# main.net
KiCad netlist of a schematic drawn in EAGLE
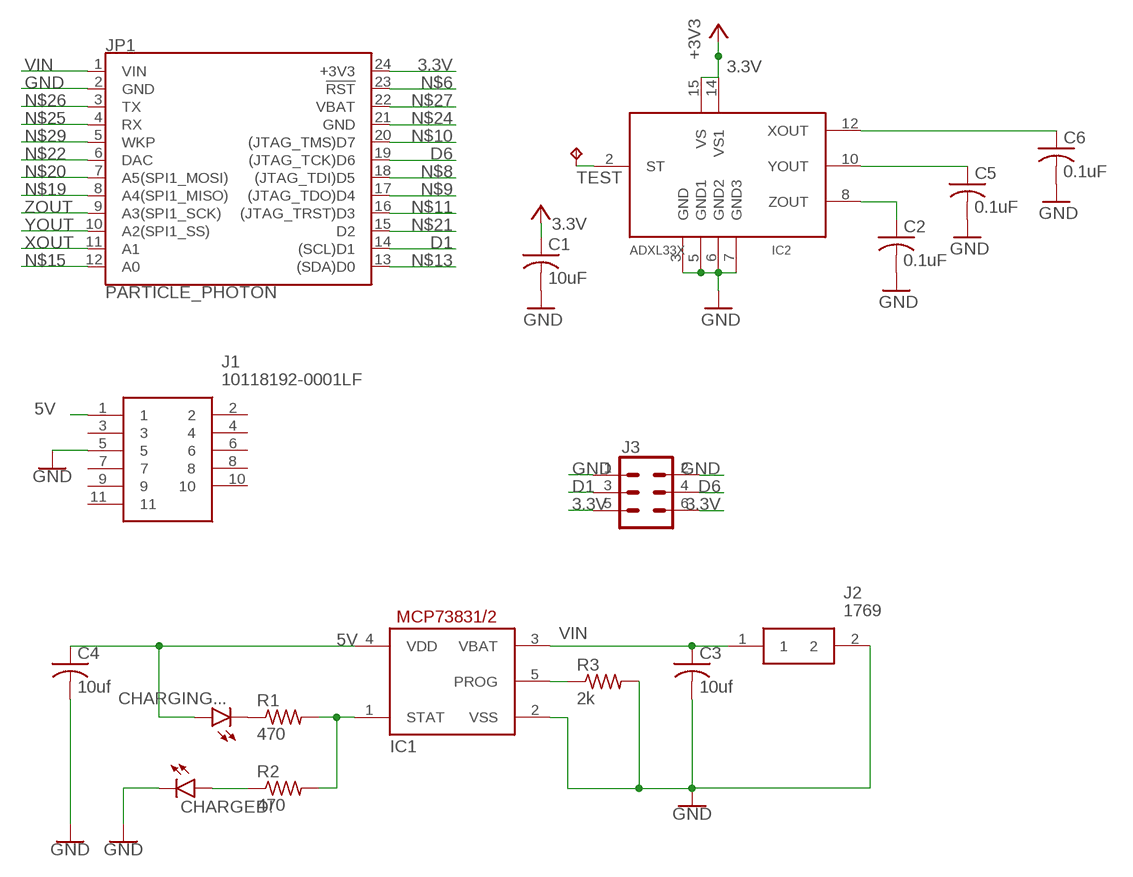
[diagram p0: schematic, sheet 1]

(export (version "E")
  (design (tool "Eeschema 10.0.6"))
  (components
    (comp (ref "C1")
      (value "10uF")
      (footprint "eagle-import:ADAFRUIT_C1206K")
      (libsource (lib "eagle-import") (part "ADAFRUIT_C-USC1206K"))
    )
    (comp (ref "C2")
      (value "0.1uF")
      (footprint "eagle-import:ADAFRUIT_C1206K")
      (libsource (lib "eagle-import") (part "ADAFRUIT_C-USC1206K"))
    )
    (comp (ref "C3")
      (value "10uf")
      (footprint "eagle-import:C1206K")
      (libsource (lib "eagle-import") (part "C-USC1206K"))
    )
    (comp (ref "C4")
      (value "10uf")
      (footprint "eagle-import:C1206K")
      (libsource (lib "eagle-import") (part "C-USC1206K"))
    )
    (comp (ref "C5")
      (value "0.1uF")
      (footprint "eagle-import:ADAFRUIT_C1206K")
      (libsource (lib "eagle-import") (part "ADAFRUIT_C-USC1206K"))
    )
    (comp (ref "C6")
      (value "0.1uF")
      (footprint "eagle-import:ADAFRUIT_C1206K")
      (libsource (lib "eagle-import") (part "ADAFRUIT_C-USC1206K"))
    )
    (comp (ref "CHARGED!")
      (value "green")
      (footprint "eagle-import:FKIT-LED-1206")
      (libsource (lib "eagle-import") (part "LED-FKIT-1206"))
    )
    (comp (ref "CHARGING...")
      (value "blue")
      (footprint "eagle-import:FKIT-LED-1206")
      (libsource (lib "eagle-import") (part "LED-FKIT-1206"))
    )
    (comp (ref "IC1")
      (value "MCP73831/OT")
      (footprint "eagle-import:SOT23-5L")
      (libsource (lib "eagle-import") (part "MCP73831/OT"))
    )
    (comp (ref "IC2")
      (value "ADXL33X")
      (footprint "eagle-import:16LCSP")
      (libsource (lib "eagle-import") (part "ADXL33X"))
    )
    (comp (ref "J1")
      (value "10118192-0001LF")
      (footprint "eagle-import:101181920001LF")
      (fields (field (name "MOUSER_PART_NUMBER") "649-10118192-0001LF"))
      (libsource (lib "eagle-import") (part "10118192-0001LF"))
    )
    (comp (ref "J2")
      (value "1769")
      (footprint "eagle-import:1769")
      (fields (field (name "MOUSER_PART_NUMBER") "485-1769"))
      (libsource (lib "eagle-import") (part "1769"))
    )
    (comp (ref "J3")
      (value "CONN_03X2FEMALE_SMD")
      (footprint "eagle-import:2X3_SMD")
      (libsource (lib "eagle-import") (part "CONN_03X2FEMALE_SMD"))
    )
    (comp (ref "JP1")
      (value "PARTICLE_PHOTON")
      (footprint "eagle-import:PARTICLE_PHOTON")
      (libsource (lib "eagle-import") (part "PARTICLE_PHOTON"))
    )
    (comp (ref "R1")
      (value "470")
      (footprint "eagle-import:M1206")
      (libsource (lib "eagle-import") (part "R-US_M1206"))
    )
    (comp (ref "R2")
      (value "470")
      (footprint "eagle-import:M1206")
      (libsource (lib "eagle-import") (part "R-US_M1206"))
    )
    (comp (ref "R3")
      (value "2k")
      (footprint "eagle-import:M1206")
      (libsource (lib "eagle-import") (part "R-US_M1206"))
    )
    (comp (ref "TEST")
      (value "TPTP14R")
      (footprint "eagle-import:TP14R")
      (libsource (lib "eagle-import") (part "TPTP14R"))
    )
  )
  (nets
    (net (code "1") (name "+3V3") (class "Default")
      (node (ref "C1") (pin "1") (pinfunction "1_1") (pintype "passive"))
      (node (ref "IC2") (pin "14") (pinfunction "VS1_14") (pintype "power_in"))
      (node (ref "IC2") (pin "15") (pinfunction "VS_15") (pintype "power_in"))
      (node (ref "J3") (pin "5") (pinfunction "5_5") (pintype "bidirectional"))
      (node (ref "J3") (pin "6") (pinfunction "6_6") (pintype "bidirectional"))
      (node (ref "JP1") (pin "24") (pinfunction "+3V3_24") (pintype "power_in"))
    )
    (net (code "2") (name "/5V") (class "Default")
      (node (ref "C4") (pin "1") (pinfunction "1_1") (pintype "passive"))
      (node (ref "CHARGING...") (pin "A") (pinfunction "A_A") (pintype "passive"))
      (node (ref "IC1") (pin "4") (pinfunction "VDD_4") (pintype "power_in"))
      (node (ref "J1") (pin "1") (pinfunction "1_1") (pintype "bidirectional"))
    )
    (net (code "3") (name "/D1") (class "Default")
      (node (ref "J3") (pin "3") (pinfunction "3_3") (pintype "bidirectional"))
      (node (ref "JP1") (pin "14") (pinfunction "(SCL)D1_14") (pintype "bidirectional"))
    )
    (net (code "4") (name "/D6") (class "Default")
      (node (ref "J3") (pin "4") (pinfunction "4_4") (pintype "bidirectional"))
      (node (ref "JP1") (pin "19") (pinfunction "(JTAG_TCK)D6_19") (pintype "bidirectional"))
    )
    (net (code "5") (name "/N$6") (class "Default")
      (node (ref "JP1") (pin "23") (pinfunction "~{RST}_23") (pintype "bidirectional"))
    )
    (net (code "6") (name "/N$8") (class "Default")
      (node (ref "JP1") (pin "18") (pinfunction "(JTAG_TDI)D5_18") (pintype "bidirectional"))
    )
    (net (code "7") (name "/N$9") (class "Default")
      (node (ref "JP1") (pin "17") (pinfunction "(JTAG_TDO)D4_17") (pintype "bidirectional"))
    )
    (net (code "8") (name "/N$10") (class "Default")
      (node (ref "JP1") (pin "20") (pinfunction "(JTAG_TMS)D7_20") (pintype "bidirectional"))
    )
    (net (code "9") (name "/N$11") (class "Default")
      (node (ref "JP1") (pin "16") (pinfunction "(JTAG_TRST)D3_16") (pintype "bidirectional"))
    )
    (net (code "10") (name "/N$13") (class "Default")
      (node (ref "JP1") (pin "13") (pinfunction "(SDA)D0_13") (pintype "bidirectional"))
    )
    (net (code "11") (name "/N$15") (class "Default")
      (node (ref "JP1") (pin "12") (pinfunction "A0_12") (pintype "bidirectional"))
    )
    (net (code "12") (name "/N$19") (class "Default")
      (node (ref "JP1") (pin "8") (pinfunction "A4(SPI1_MISO)_8") (pintype "bidirectional"))
    )
    (net (code "13") (name "/N$20") (class "Default")
      (node (ref "JP1") (pin "7") (pinfunction "A5(SPI1_MOSI)_7") (pintype "bidirectional"))
    )
    (net (code "14") (name "/N$21") (class "Default")
      (node (ref "JP1") (pin "15") (pinfunction "D2_15") (pintype "bidirectional"))
    )
    (net (code "15") (name "/N$22") (class "Default")
      (node (ref "JP1") (pin "6") (pinfunction "DAC_6") (pintype "bidirectional"))
    )
    (net (code "16") (name "/N$24") (class "Default")
      (node (ref "JP1") (pin "21") (pinfunction "GND_21") (pintype "power_in"))
    )
    (net (code "17") (name "/N$25") (class "Default")
      (node (ref "JP1") (pin "4") (pinfunction "RX_4") (pintype "bidirectional"))
    )
    (net (code "18") (name "/N$26") (class "Default")
      (node (ref "JP1") (pin "3") (pinfunction "TX_3") (pintype "bidirectional"))
    )
    (net (code "19") (name "/N$27") (class "Default")
      (node (ref "JP1") (pin "22") (pinfunction "VBAT_22") (pintype "power_in"))
    )
    (net (code "20") (name "/N$29") (class "Default")
      (node (ref "JP1") (pin "5") (pinfunction "WKP_5") (pintype "bidirectional"))
    )
    (net (code "21") (name "/TEST") (class "Default")
      (node (ref "IC2") (pin "2") (pinfunction "ST_2") (pintype "input"))
      (node (ref "TEST") (pin "TP") (pinfunction "TP_TP") (pintype "input"))
    )
    (net (code "22") (name "/VIN") (class "Default")
      (node (ref "C3") (pin "1") (pinfunction "1_1") (pintype "passive"))
      (node (ref "IC1") (pin "3") (pinfunction "VBAT_3") (pintype "bidirectional"))
      (node (ref "J2") (pin "1") (pinfunction "1_1") (pintype "bidirectional"))
      (node (ref "JP1") (pin "1") (pinfunction "VIN_1") (pintype "power_in"))
    )
    (net (code "23") (name "/XOUT") (class "Default")
      (node (ref "C6") (pin "1") (pinfunction "1_1") (pintype "passive"))
      (node (ref "IC2") (pin "12") (pinfunction "XOUT_12") (pintype "output"))
      (node (ref "JP1") (pin "11") (pinfunction "A1_11") (pintype "bidirectional"))
    )
    (net (code "24") (name "/YOUT") (class "Default")
      (node (ref "C5") (pin "1") (pinfunction "1_1") (pintype "passive"))
      (node (ref "IC2") (pin "10") (pinfunction "YOUT_10") (pintype "output"))
      (node (ref "JP1") (pin "10") (pinfunction "A2(SPI1_SS)_10") (pintype "bidirectional"))
    )
    (net (code "25") (name "/ZOUT") (class "Default")
      (node (ref "C2") (pin "1") (pinfunction "1_1") (pintype "passive"))
      (node (ref "IC2") (pin "8") (pinfunction "ZOUT_8") (pintype "output"))
      (node (ref "JP1") (pin "9") (pinfunction "A3(SPI1_SCK)_9") (pintype "bidirectional"))
    )
    (net (code "26") (name "GND") (class "Default")
      (node (ref "C1") (pin "2") (pinfunction "2_2") (pintype "passive"))
      (node (ref "C2") (pin "2") (pinfunction "2_2") (pintype "passive"))
      (node (ref "C3") (pin "2") (pinfunction "2_2") (pintype "passive"))
      (node (ref "C4") (pin "2") (pinfunction "2_2") (pintype "passive"))
      (node (ref "C5") (pin "2") (pinfunction "2_2") (pintype "passive"))
      (node (ref "C6") (pin "2") (pinfunction "2_2") (pintype "passive"))
      (node (ref "CHARGED!") (pin "C") (pinfunction "C_C") (pintype "passive"))
      (node (ref "IC1") (pin "2") (pinfunction "VSS_2") (pintype "power_in"))
      (node (ref "IC2") (pin "3") (pinfunction "GND_3") (pintype "power_in"))
      (node (ref "IC2") (pin "5") (pinfunction "GND1_5") (pintype "power_in"))
      (node (ref "IC2") (pin "6") (pinfunction "GND2_6") (pintype "power_in"))
      (node (ref "IC2") (pin "7") (pinfunction "GND3_7") (pintype "power_in"))
      (node (ref "J1") (pin "5") (pinfunction "5_5") (pintype "bidirectional"))
      (node (ref "J2") (pin "2") (pinfunction "2_2") (pintype "bidirectional"))
      (node (ref "J3") (pin "1") (pinfunction "1_1") (pintype "bidirectional"))
      (node (ref "J3") (pin "2") (pinfunction "2_2") (pintype "bidirectional"))
      (node (ref "JP1") (pin "2") (pinfunction "GND_2") (pintype "power_in"))
      (node (ref "R3") (pin "2") (pinfunction "2_2") (pintype "passive"))
    )
    (net (code "27") (name "Net-(CHARGED!-PadA)") (class "Default")
      (node (ref "CHARGED!") (pin "A") (pinfunction "A_A") (pintype "passive"))
      (node (ref "R2") (pin "1") (pinfunction "1_1") (pintype "passive"))
    )
    (net (code "28") (name "Net-(CHARGING...-PadC)") (class "Default")
      (node (ref "CHARGING...") (pin "C") (pinfunction "C_C") (pintype "passive"))
      (node (ref "R1") (pin "1") (pinfunction "1_1") (pintype "passive"))
    )
    (net (code "29") (name "Net-(IC1-PROG)") (class "Default")
      (node (ref "IC1") (pin "5") (pinfunction "PROG_5") (pintype "input"))
      (node (ref "R3") (pin "1") (pinfunction "1_1") (pintype "passive"))
    )
    (net (code "30") (name "Net-(IC1-STAT)") (class "Default")
      (node (ref "IC1") (pin "1") (pinfunction "STAT_1") (pintype "output"))
      (node (ref "R1") (pin "2") (pinfunction "2_2") (pintype "passive"))
      (node (ref "R2") (pin "2") (pinfunction "2_2") (pintype "passive"))
    )
    (net (code "31") (name "unconnected-(J1-Pad2)") (class "Default")
      (node (ref "J1") (pin "2") (pinfunction "2_2") (pintype "bidirectional"))
    )
    (net (code "32") (name "unconnected-(J1-Pad3)") (class "Default")
      (node (ref "J1") (pin "3") (pinfunction "3_3") (pintype "bidirectional"))
    )
    (net (code "33") (name "unconnected-(J1-Pad4)") (class "Default")
      (node (ref "J1") (pin "4") (pinfunction "4_4") (pintype "bidirectional"))
    )
    (net (code "34") (name "unconnected-(J1-Pad6)") (class "Default")
      (node (ref "J1") (pin "6") (pinfunction "6_6") (pintype "bidirectional"))
    )
    (net (code "35") (name "unconnected-(J1-Pad7)") (class "Default")
      (node (ref "J1") (pin "7") (pinfunction "7_7") (pintype "bidirectional"))
    )
    (net (code "36") (name "unconnected-(J1-Pad8)") (class "Default")
      (node (ref "J1") (pin "8") (pinfunction "8_8") (pintype "bidirectional"))
    )
    (net (code "37") (name "unconnected-(J1-Pad9)") (class "Default")
      (node (ref "J1") (pin "9") (pinfunction "9_9") (pintype "bidirectional"))
    )
    (net (code "38") (name "unconnected-(J1-Pad10)") (class "Default")
      (node (ref "J1") (pin "10") (pinfunction "10_10") (pintype "bidirectional"))
    )
    (net (code "39") (name "unconnected-(J1-Pad11)") (class "Default")
      (node (ref "J1") (pin "11") (pinfunction "11_11") (pintype "bidirectional"))
    )
  )
)
